# tree.net
KiCad netlist of a schematic drawn in EAGLE
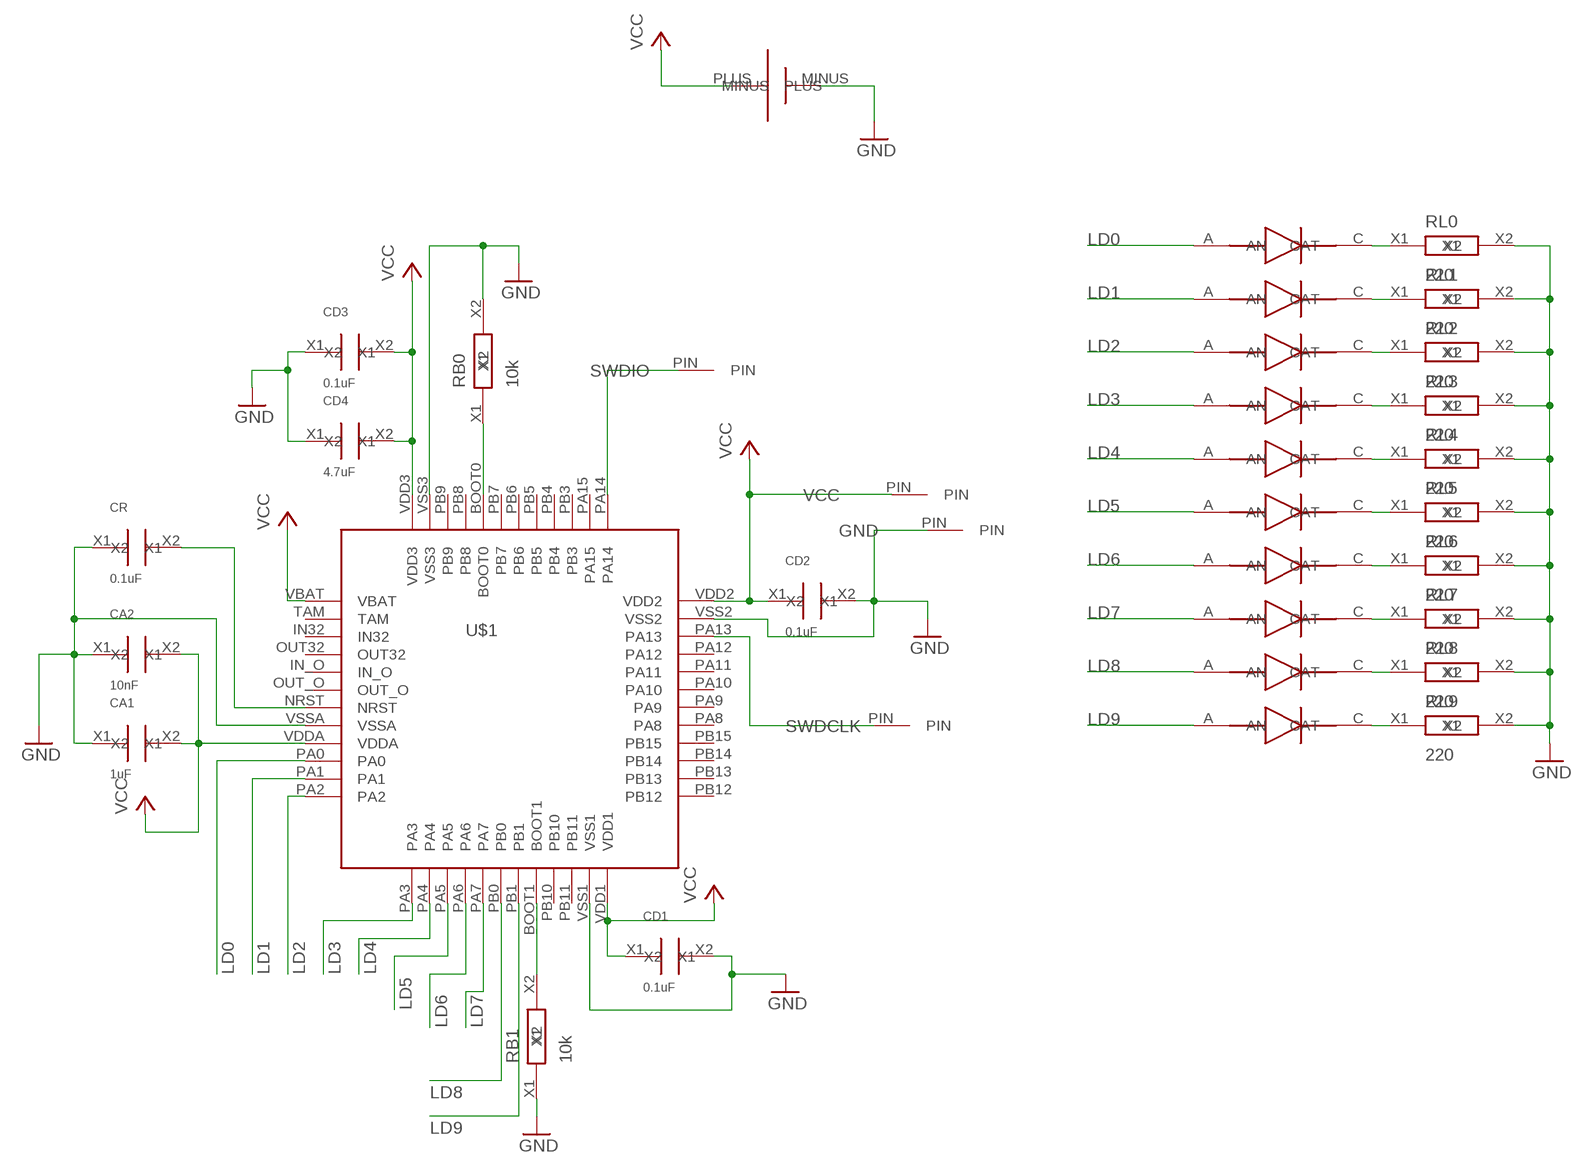
[diagram p0: schematic, sheet 1]

(export (version "E")
  (design (tool "Eeschema 10.0.6"))
  (components
    (comp (ref "CA1")
      (value "1uF")
      (footprint "eagle-import:SMD_2.1X1.25")
      (libsource (lib "eagle-import") (part "C_SMD_2.1X1.25"))
    )
    (comp (ref "CA2")
      (value "10nF")
      (footprint "eagle-import:SMD_2.1X1.25")
      (libsource (lib "eagle-import") (part "C_SMD_2.1X1.25"))
    )
    (comp (ref "CD1")
      (value "0.1uF")
      (footprint "eagle-import:SMD_2.1X1.25")
      (libsource (lib "eagle-import") (part "C_SMD_2.1X1.25"))
    )
    (comp (ref "CD2")
      (value "0.1uF")
      (footprint "eagle-import:SMD_2.1X1.25")
      (libsource (lib "eagle-import") (part "C_SMD_2.1X1.25"))
    )
    (comp (ref "CD3")
      (value "0.1uF")
      (footprint "eagle-import:SMD_2.1X1.25")
      (libsource (lib "eagle-import") (part "C_SMD_2.1X1.25"))
    )
    (comp (ref "CD4")
      (value "4.7uF")
      (footprint "eagle-import:SMD_2.1X1.25")
      (libsource (lib "eagle-import") (part "C_SMD_2.1X1.25"))
    )
    (comp (ref "CR")
      (value "0.1uF")
      (footprint "eagle-import:SMD_2.1X1.25")
      (libsource (lib "eagle-import") (part "C_SMD_2.1X1.25"))
    )
    (comp (ref "GND")
      (value "PIN_06")
      (footprint "eagle-import:PIN_06")
      (libsource (lib "eagle-import") (part "PIN_06"))
    )
    (comp (ref "RB0")
      (value "10k")
      (footprint "eagle-import:SMD_2.1X1.25")
      (libsource (lib "eagle-import") (part "R_SMD_2.1X1.25"))
    )
    (comp (ref "RB1")
      (value "10k")
      (footprint "eagle-import:SMD_2.1X1.25")
      (libsource (lib "eagle-import") (part "R_SMD_2.1X1.25"))
    )
    (comp (ref "RL0")
      (value "220")
      (footprint "eagle-import:SMD_2.1X1.25")
      (libsource (lib "eagle-import") (part "R_SMD_2.1X1.25"))
    )
    (comp (ref "RL1")
      (value "220")
      (footprint "eagle-import:SMD_2.1X1.25")
      (libsource (lib "eagle-import") (part "R_SMD_2.1X1.25"))
    )
    (comp (ref "RL2")
      (value "220")
      (footprint "eagle-import:SMD_2.1X1.25")
      (libsource (lib "eagle-import") (part "R_SMD_2.1X1.25"))
    )
    (comp (ref "RL3")
      (value "220")
      (footprint "eagle-import:SMD_2.1X1.25")
      (libsource (lib "eagle-import") (part "R_SMD_2.1X1.25"))
    )
    (comp (ref "RL4")
      (value "220")
      (footprint "eagle-import:SMD_2.1X1.25")
      (libsource (lib "eagle-import") (part "R_SMD_2.1X1.25"))
    )
    (comp (ref "RL5")
      (value "220")
      (footprint "eagle-import:SMD_2.1X1.25")
      (libsource (lib "eagle-import") (part "R_SMD_2.1X1.25"))
    )
    (comp (ref "RL6")
      (value "220")
      (footprint "eagle-import:SMD_2.1X1.25")
      (libsource (lib "eagle-import") (part "R_SMD_2.1X1.25"))
    )
    (comp (ref "RL7")
      (value "220")
      (footprint "eagle-import:SMD_2.1X1.25")
      (libsource (lib "eagle-import") (part "R_SMD_2.1X1.25"))
    )
    (comp (ref "RL8")
      (value "220")
      (footprint "eagle-import:SMD_2.1X1.25")
      (libsource (lib "eagle-import") (part "R_SMD_2.1X1.25"))
    )
    (comp (ref "RL9")
      (value "220")
      (footprint "eagle-import:SMD_2.1X1.25")
      (libsource (lib "eagle-import") (part "R_SMD_2.1X1.25"))
    )
    (comp (ref "SWDCLK")
      (value "PIN_06")
      (footprint "eagle-import:PIN_06")
      (libsource (lib "eagle-import") (part "PIN_06"))
    )
    (comp (ref "SWDIO")
      (value "PIN_06")
      (footprint "eagle-import:PIN_06")
      (libsource (lib "eagle-import") (part "PIN_06"))
    )
    (comp (ref "U$1")
      (value "STM32F103CBT6")
      (footprint "eagle-import:STM32F103CBT6")
      (libsource (lib "eagle-import") (part "STM32F103CBT6"))
    )
    (comp (ref "U$2")
      (value "LED0805")
      (footprint "eagle-import:LED0805")
      (libsource (lib "eagle-import") (part "LED0805"))
    )
    (comp (ref "U$3")
      (value "LED0805")
      (footprint "eagle-import:LED0805")
      (libsource (lib "eagle-import") (part "LED0805"))
    )
    (comp (ref "U$4")
      (value "LED0805")
      (footprint "eagle-import:LED0805")
      (libsource (lib "eagle-import") (part "LED0805"))
    )
    (comp (ref "U$5")
      (value "LED0805")
      (footprint "eagle-import:LED0805")
      (libsource (lib "eagle-import") (part "LED0805"))
    )
    (comp (ref "U$6")
      (value "LED0805")
      (footprint "eagle-import:LED0805")
      (libsource (lib "eagle-import") (part "LED0805"))
    )
    (comp (ref "U$7")
      (value "LED0805")
      (footprint "eagle-import:LED0805")
      (libsource (lib "eagle-import") (part "LED0805"))
    )
    (comp (ref "U$8")
      (value "LED0805")
      (footprint "eagle-import:LED0805")
      (libsource (lib "eagle-import") (part "LED0805"))
    )
    (comp (ref "U$9")
      (value "LED0805")
      (footprint "eagle-import:LED0805")
      (libsource (lib "eagle-import") (part "LED0805"))
    )
    (comp (ref "U$10")
      (value "LED0805")
      (footprint "eagle-import:LED0805")
      (libsource (lib "eagle-import") (part "LED0805"))
    )
    (comp (ref "U$11")
      (value "LED0805")
      (footprint "eagle-import:LED0805")
      (libsource (lib "eagle-import") (part "LED0805"))
    )
    (comp (ref "U$12")
      (value "VBAT")
      (footprint "eagle-import:VBAT")
      (libsource (lib "eagle-import") (part "VBAT"))
    )
    (comp (ref "VCC")
      (value "PIN_06")
      (footprint "eagle-import:PIN_06")
      (libsource (lib "eagle-import") (part "PIN_06"))
    )
  )
  (nets
    (net (code "1") (name "/LD0") (class "Default")
      (node (ref "U$1") (pin "PA0") (pinfunction "PA0_PA0") (pintype "bidirectional"))
      (node (ref "U$4") (pin "A") (pinfunction "AN_A") (pintype "bidirectional"))
    )
    (net (code "2") (name "/LD1") (class "Default")
      (node (ref "U$1") (pin "PA1") (pinfunction "PA1_PA1") (pintype "bidirectional"))
      (node (ref "U$2") (pin "A") (pinfunction "AN_A") (pintype "bidirectional"))
    )
    (net (code "3") (name "/LD2") (class "Default")
      (node (ref "U$1") (pin "PA2") (pinfunction "PA2_PA2") (pintype "bidirectional"))
      (node (ref "U$3") (pin "A") (pinfunction "AN_A") (pintype "bidirectional"))
    )
    (net (code "4") (name "/LD3") (class "Default")
      (node (ref "U$1") (pin "PA3") (pinfunction "PA3_PA3") (pintype "bidirectional"))
      (node (ref "U$5") (pin "A") (pinfunction "AN_A") (pintype "bidirectional"))
    )
    (net (code "5") (name "/LD4") (class "Default")
      (node (ref "U$1") (pin "PA4") (pinfunction "PA4_PA4") (pintype "bidirectional"))
      (node (ref "U$6") (pin "A") (pinfunction "AN_A") (pintype "bidirectional"))
    )
    (net (code "6") (name "/LD5") (class "Default")
      (node (ref "U$1") (pin "PA5") (pinfunction "PA5_PA5") (pintype "bidirectional"))
      (node (ref "U$7") (pin "A") (pinfunction "AN_A") (pintype "bidirectional"))
    )
    (net (code "7") (name "/LD6") (class "Default")
      (node (ref "U$1") (pin "PA6") (pinfunction "PA6_PA6") (pintype "bidirectional"))
      (node (ref "U$8") (pin "A") (pinfunction "AN_A") (pintype "bidirectional"))
    )
    (net (code "8") (name "/LD7") (class "Default")
      (node (ref "U$1") (pin "PA7") (pinfunction "PA7_PA7") (pintype "bidirectional"))
      (node (ref "U$9") (pin "A") (pinfunction "AN_A") (pintype "bidirectional"))
    )
    (net (code "9") (name "/LD8") (class "Default")
      (node (ref "U$1") (pin "PB0") (pinfunction "PB0_PB0") (pintype "bidirectional"))
      (node (ref "U$10") (pin "A") (pinfunction "AN_A") (pintype "bidirectional"))
    )
    (net (code "10") (name "/LD9") (class "Default")
      (node (ref "U$1") (pin "PB1") (pinfunction "PB1_PB1") (pintype "bidirectional"))
      (node (ref "U$11") (pin "A") (pinfunction "AN_A") (pintype "bidirectional"))
    )
    (net (code "11") (name "GND") (class "Default")
      (node (ref "CA1") (pin "X1") (pinfunction "X1_X1") (pintype "bidirectional"))
      (node (ref "CA2") (pin "X1") (pinfunction "X1_X1") (pintype "bidirectional"))
      (node (ref "CD1") (pin "X2") (pinfunction "X2_X2") (pintype "bidirectional"))
      (node (ref "CD2") (pin "X2") (pinfunction "X2_X2") (pintype "bidirectional"))
      (node (ref "CD3") (pin "X1") (pinfunction "X1_X1") (pintype "bidirectional"))
      (node (ref "CD4") (pin "X1") (pinfunction "X1_X1") (pintype "bidirectional"))
      (node (ref "CR") (pin "X1") (pinfunction "X1_X1") (pintype "bidirectional"))
      (node (ref "GND") (pin "PIN") (pinfunction "PIN_PIN") (pintype "bidirectional"))
      (node (ref "RB0") (pin "X2") (pinfunction "X2_X2") (pintype "bidirectional"))
      (node (ref "RB1") (pin "X1") (pinfunction "X1_X1") (pintype "bidirectional"))
      (node (ref "RL0") (pin "X2") (pinfunction "X2_X2") (pintype "bidirectional"))
      (node (ref "RL1") (pin "X2") (pinfunction "X2_X2") (pintype "bidirectional"))
      (node (ref "RL2") (pin "X2") (pinfunction "X2_X2") (pintype "bidirectional"))
      (node (ref "RL3") (pin "X2") (pinfunction "X2_X2") (pintype "bidirectional"))
      (node (ref "RL4") (pin "X2") (pinfunction "X2_X2") (pintype "bidirectional"))
      (node (ref "RL5") (pin "X2") (pinfunction "X2_X2") (pintype "bidirectional"))
      (node (ref "RL6") (pin "X2") (pinfunction "X2_X2") (pintype "bidirectional"))
      (node (ref "RL7") (pin "X2") (pinfunction "X2_X2") (pintype "bidirectional"))
      (node (ref "RL8") (pin "X2") (pinfunction "X2_X2") (pintype "bidirectional"))
      (node (ref "RL9") (pin "X2") (pinfunction "X2_X2") (pintype "bidirectional"))
      (node (ref "U$1") (pin "VSS1") (pinfunction "VSS1_VSS1") (pintype "bidirectional"))
      (node (ref "U$1") (pin "VSS2") (pinfunction "VSS2_VSS2") (pintype "bidirectional"))
      (node (ref "U$1") (pin "VSS3") (pinfunction "VSS3_VSS3") (pintype "bidirectional"))
      (node (ref "U$1") (pin "VSSA") (pinfunction "VSSA_VSSA") (pintype "bidirectional"))
      (node (ref "U$12") (pin "MINUS") (pinfunction "MINUS_MINUS") (pintype "bidirectional"))
    )
    (net (code "12") (name "Net-(CR-PadX2)") (class "Default")
      (node (ref "CR") (pin "X2") (pinfunction "X2_X2") (pintype "bidirectional"))
      (node (ref "U$1") (pin "NRST") (pinfunction "NRST_NRST") (pintype "bidirectional"))
    )
    (net (code "13") (name "Net-(RB0-PadX1)") (class "Default")
      (node (ref "RB0") (pin "X1") (pinfunction "X1_X1") (pintype "bidirectional"))
      (node (ref "U$1") (pin "BOOT0") (pinfunction "BOOT0_BOOT0") (pintype "bidirectional"))
    )
    (net (code "14") (name "Net-(RB1-PadX2)") (class "Default")
      (node (ref "RB1") (pin "X2") (pinfunction "X2_X2") (pintype "bidirectional"))
      (node (ref "U$1") (pin "BOOT1") (pinfunction "BOOT1_BOOT1") (pintype "bidirectional"))
    )
    (net (code "15") (name "Net-(SWDCLK-PadPIN)") (class "Default")
      (node (ref "SWDCLK") (pin "PIN") (pinfunction "PIN_PIN") (pintype "bidirectional"))
      (node (ref "U$1") (pin "PA13") (pinfunction "PA13_PA13") (pintype "bidirectional"))
    )
    (net (code "16") (name "Net-(SWDIO-PadPIN)") (class "Default")
      (node (ref "SWDIO") (pin "PIN") (pinfunction "PIN_PIN") (pintype "bidirectional"))
      (node (ref "U$1") (pin "PA14") (pinfunction "PA14_PA14") (pintype "bidirectional"))
    )
    (net (code "17") (name "Net-(U$2-CAT)") (class "Default")
      (node (ref "RL1") (pin "X1") (pinfunction "X1_X1") (pintype "bidirectional"))
      (node (ref "U$2") (pin "C") (pinfunction "CAT_C") (pintype "bidirectional"))
    )
    (net (code "18") (name "Net-(U$3-CAT)") (class "Default")
      (node (ref "RL2") (pin "X1") (pinfunction "X1_X1") (pintype "bidirectional"))
      (node (ref "U$3") (pin "C") (pinfunction "CAT_C") (pintype "bidirectional"))
    )
    (net (code "19") (name "Net-(U$4-CAT)") (class "Default")
      (node (ref "RL0") (pin "X1") (pinfunction "X1_X1") (pintype "bidirectional"))
      (node (ref "U$4") (pin "C") (pinfunction "CAT_C") (pintype "bidirectional"))
    )
    (net (code "20") (name "Net-(U$5-CAT)") (class "Default")
      (node (ref "RL3") (pin "X1") (pinfunction "X1_X1") (pintype "bidirectional"))
      (node (ref "U$5") (pin "C") (pinfunction "CAT_C") (pintype "bidirectional"))
    )
    (net (code "21") (name "Net-(U$6-CAT)") (class "Default")
      (node (ref "RL4") (pin "X1") (pinfunction "X1_X1") (pintype "bidirectional"))
      (node (ref "U$6") (pin "C") (pinfunction "CAT_C") (pintype "bidirectional"))
    )
    (net (code "22") (name "Net-(U$7-CAT)") (class "Default")
      (node (ref "RL5") (pin "X1") (pinfunction "X1_X1") (pintype "bidirectional"))
      (node (ref "U$7") (pin "C") (pinfunction "CAT_C") (pintype "bidirectional"))
    )
    (net (code "23") (name "Net-(U$8-CAT)") (class "Default")
      (node (ref "RL6") (pin "X1") (pinfunction "X1_X1") (pintype "bidirectional"))
      (node (ref "U$8") (pin "C") (pinfunction "CAT_C") (pintype "bidirectional"))
    )
    (net (code "24") (name "Net-(U$9-CAT)") (class "Default")
      (node (ref "RL7") (pin "X1") (pinfunction "X1_X1") (pintype "bidirectional"))
      (node (ref "U$9") (pin "C") (pinfunction "CAT_C") (pintype "bidirectional"))
    )
    (net (code "25") (name "Net-(U$10-CAT)") (class "Default")
      (node (ref "RL8") (pin "X1") (pinfunction "X1_X1") (pintype "bidirectional"))
      (node (ref "U$10") (pin "C") (pinfunction "CAT_C") (pintype "bidirectional"))
    )
    (net (code "26") (name "Net-(U$11-CAT)") (class "Default")
      (node (ref "RL9") (pin "X1") (pinfunction "X1_X1") (pintype "bidirectional"))
      (node (ref "U$11") (pin "C") (pinfunction "CAT_C") (pintype "bidirectional"))
    )
    (net (code "27") (name "VCC") (class "Default")
      (node (ref "CA1") (pin "X2") (pinfunction "X2_X2") (pintype "bidirectional"))
      (node (ref "CA2") (pin "X2") (pinfunction "X2_X2") (pintype "bidirectional"))
      (node (ref "CD1") (pin "X1") (pinfunction "X1_X1") (pintype "bidirectional"))
      (node (ref "CD2") (pin "X1") (pinfunction "X1_X1") (pintype "bidirectional"))
      (node (ref "CD3") (pin "X2") (pinfunction "X2_X2") (pintype "bidirectional"))
      (node (ref "CD4") (pin "X2") (pinfunction "X2_X2") (pintype "bidirectional"))
      (node (ref "U$1") (pin "VBAT") (pinfunction "VBAT_VBAT") (pintype "bidirectional"))
      (node (ref "U$1") (pin "VDD1") (pinfunction "VDD1_VDD1") (pintype "bidirectional"))
      (node (ref "U$1") (pin "VDD2") (pinfunction "VDD2_VDD2") (pintype "bidirectional"))
      (node (ref "U$1") (pin "VDD3") (pinfunction "VDD3_VDD3") (pintype "bidirectional"))
      (node (ref "U$1") (pin "VDDA") (pinfunction "VDDA_VDDA") (pintype "bidirectional"))
      (node (ref "U$12") (pin "PLUS") (pinfunction "PLUS_PLUS") (pintype "bidirectional"))
      (node (ref "VCC") (pin "PIN") (pinfunction "PIN_PIN") (pintype "bidirectional"))
    )
    (net (code "28") (name "unconnected-(U$1-PadIN32)") (class "Default")
      (node (ref "U$1") (pin "IN32") (pinfunction "IN32_IN32") (pintype "bidirectional"))
    )
    (net (code "29") (name "unconnected-(U$1-PadIN_O)") (class "Default")
      (node (ref "U$1") (pin "IN_O") (pinfunction "IN_O_IN_O") (pintype "bidirectional"))
    )
    (net (code "30") (name "unconnected-(U$1-PadOUT32)") (class "Default")
      (node (ref "U$1") (pin "OUT32") (pinfunction "OUT32_OUT32") (pintype "bidirectional"))
    )
    (net (code "31") (name "unconnected-(U$1-PadOUT_O)") (class "Default")
      (node (ref "U$1") (pin "OUT_O") (pinfunction "OUT_O_OUT_O") (pintype "bidirectional"))
    )
    (net (code "32") (name "unconnected-(U$1-PadPA8)") (class "Default")
      (node (ref "U$1") (pin "PA8") (pinfunction "PA8_PA8") (pintype "bidirectional"))
    )
    (net (code "33") (name "unconnected-(U$1-PadPA9)") (class "Default")
      (node (ref "U$1") (pin "PA9") (pinfunction "PA9_PA9") (pintype "bidirectional"))
    )
    (net (code "34") (name "unconnected-(U$1-PadPA10)") (class "Default")
      (node (ref "U$1") (pin "PA10") (pinfunction "PA10_PA10") (pintype "bidirectional"))
    )
    (net (code "35") (name "unconnected-(U$1-PadPA11)") (class "Default")
      (node (ref "U$1") (pin "PA11") (pinfunction "PA11_PA11") (pintype "bidirectional"))
    )
    (net (code "36") (name "unconnected-(U$1-PadPA12)") (class "Default")
      (node (ref "U$1") (pin "PA12") (pinfunction "PA12_PA12") (pintype "bidirectional"))
    )
    (net (code "37") (name "unconnected-(U$1-PadPA15)") (class "Default")
      (node (ref "U$1") (pin "PA15") (pinfunction "PA15_PA15") (pintype "bidirectional"))
    )
    (net (code "38") (name "unconnected-(U$1-PadPB3)") (class "Default")
      (node (ref "U$1") (pin "PB3") (pinfunction "PB3_PB3") (pintype "bidirectional"))
    )
    (net (code "39") (name "unconnected-(U$1-PadPB4)") (class "Default")
      (node (ref "U$1") (pin "PB4") (pinfunction "PB4_PB4") (pintype "bidirectional"))
    )
    (net (code "40") (name "unconnected-(U$1-PadPB5)") (class "Default")
      (node (ref "U$1") (pin "PB5") (pinfunction "PB5_PB5") (pintype "bidirectional"))
    )
    (net (code "41") (name "unconnected-(U$1-PadPB6)") (class "Default")
      (node (ref "U$1") (pin "PB6") (pinfunction "PB6_PB6") (pintype "bidirectional"))
    )
    (net (code "42") (name "unconnected-(U$1-PadPB7)") (class "Default")
      (node (ref "U$1") (pin "PB7") (pinfunction "PB7_PB7") (pintype "bidirectional"))
    )
    (net (code "43") (name "unconnected-(U$1-PadPB8)") (class "Default")
      (node (ref "U$1") (pin "PB8") (pinfunction "PB8_PB8") (pintype "bidirectional"))
    )
    (net (code "44") (name "unconnected-(U$1-PadPB9)") (class "Default")
      (node (ref "U$1") (pin "PB9") (pinfunction "PB9_PB9") (pintype "bidirectional"))
    )
    (net (code "45") (name "unconnected-(U$1-PadPB10)") (class "Default")
      (node (ref "U$1") (pin "PB10") (pinfunction "PB10_PB10") (pintype "bidirectional"))
    )
    (net (code "46") (name "unconnected-(U$1-PadPB11)") (class "Default")
      (node (ref "U$1") (pin "PB11") (pinfunction "PB11_PB11") (pintype "bidirectional"))
    )
    (net (code "47") (name "unconnected-(U$1-PadPB12)") (class "Default")
      (node (ref "U$1") (pin "PB12") (pinfunction "PB12_PB12") (pintype "bidirectional"))
    )
    (net (code "48") (name "unconnected-(U$1-PadPB13)") (class "Default")
      (node (ref "U$1") (pin "PB13") (pinfunction "PB13_PB13") (pintype "bidirectional"))
    )
    (net (code "49") (name "unconnected-(U$1-PadPB14)") (class "Default")
      (node (ref "U$1") (pin "PB14") (pinfunction "PB14_PB14") (pintype "bidirectional"))
    )
    (net (code "50") (name "unconnected-(U$1-PadPB15)") (class "Default")
      (node (ref "U$1") (pin "PB15") (pinfunction "PB15_PB15") (pintype "bidirectional"))
    )
    (net (code "51") (name "unconnected-(U$1-PadTAM)") (class "Default")
      (node (ref "U$1") (pin "TAM") (pinfunction "TAM_TAM") (pintype "bidirectional"))
    )
  )
)
